# BLE1.net
KiCad netlist of a schematic drawn in EasyEDA Pro
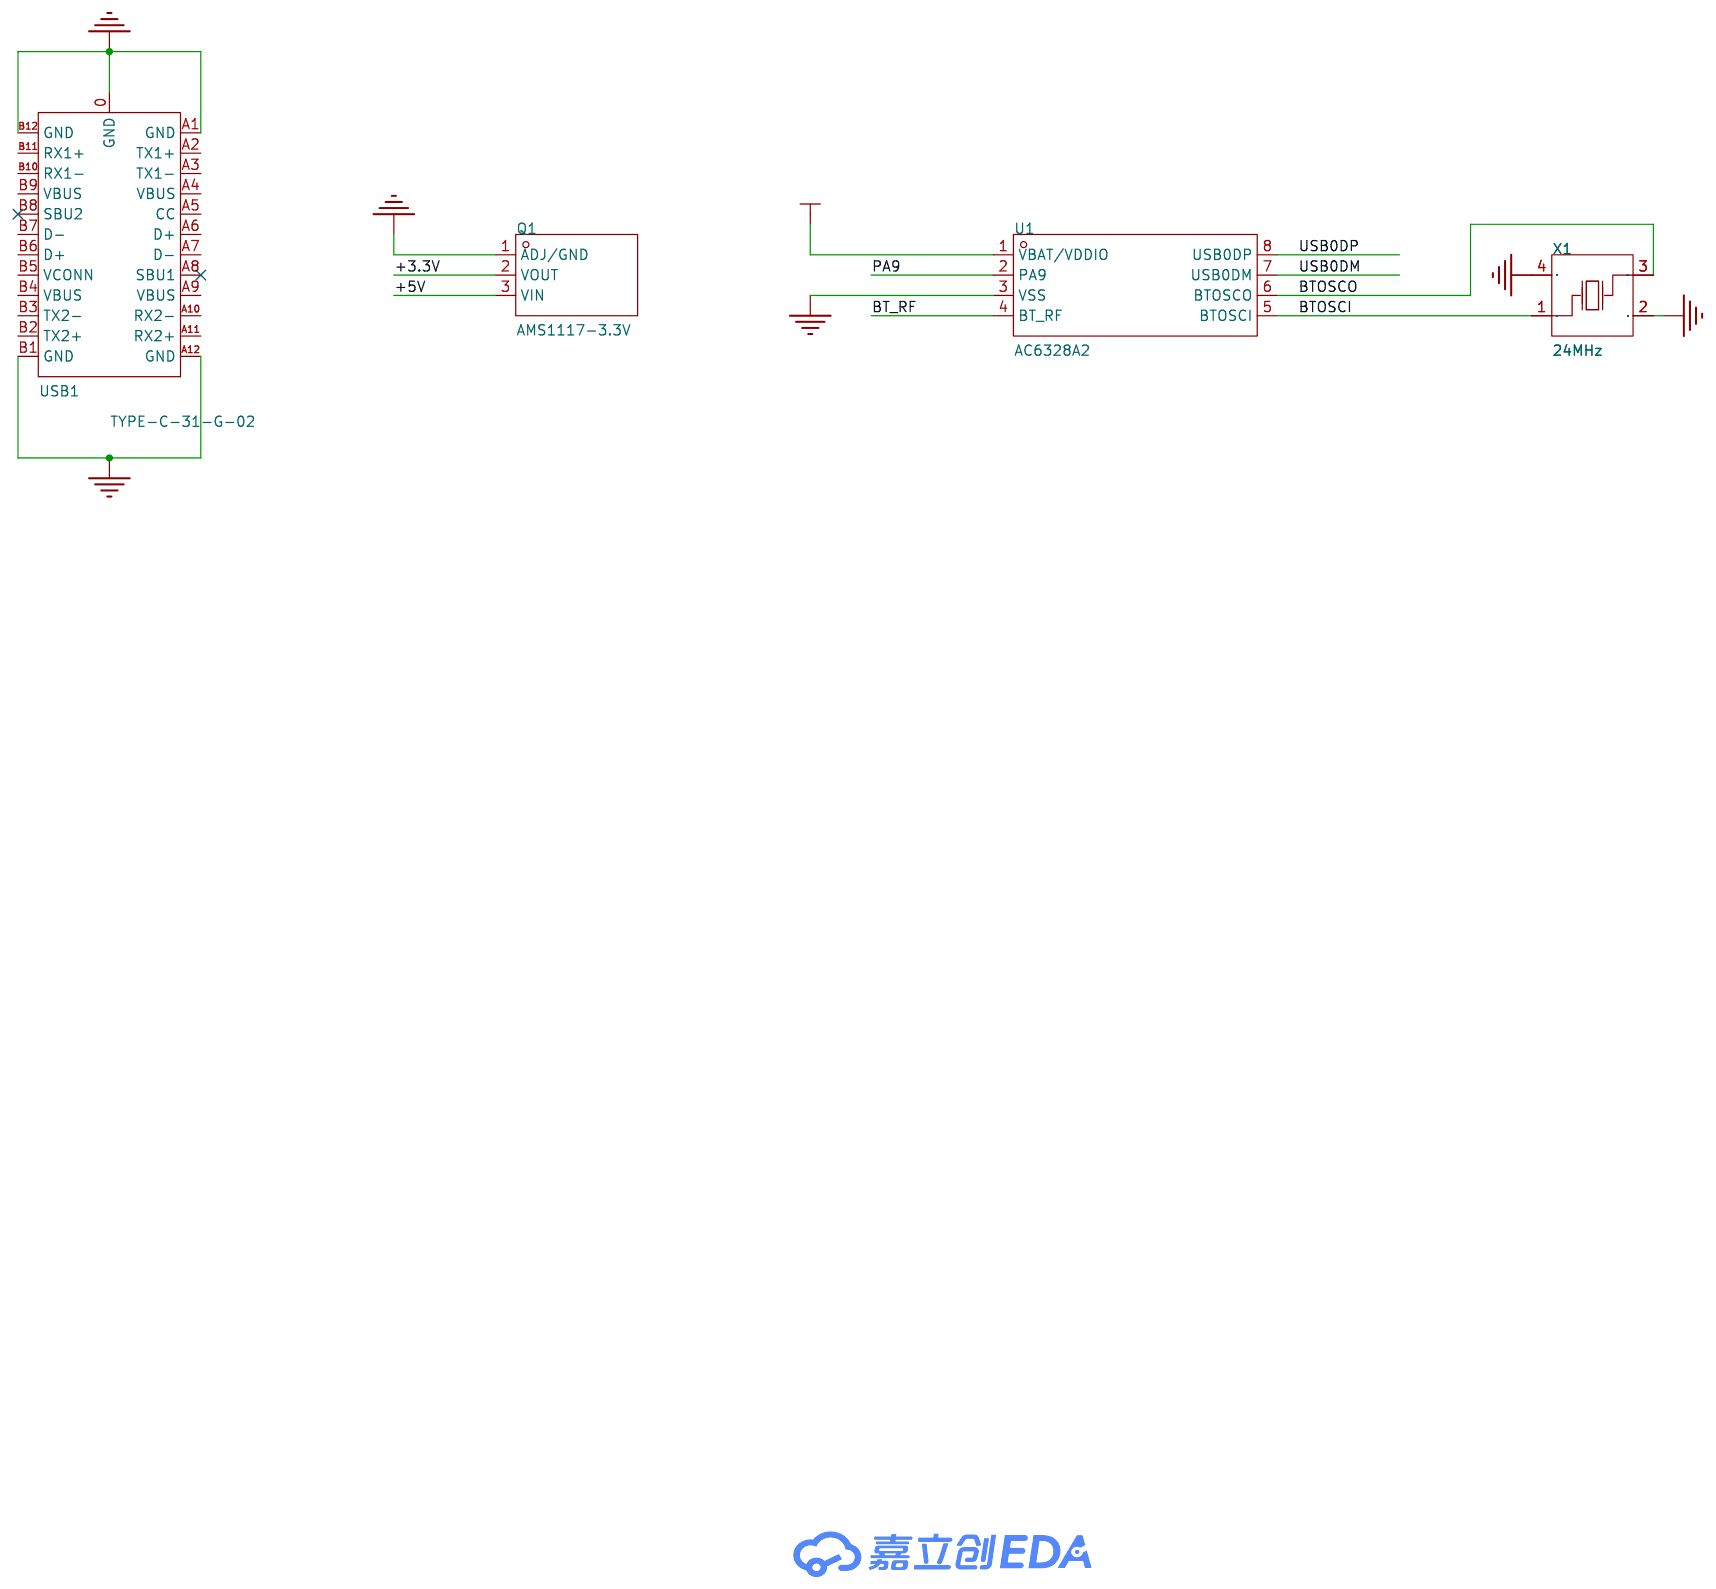
[diagram p0: schematic sheet]

(export (version "E")
  (design (tool "Eeschema 10.0.6"))
  (components
    (comp (ref "Q1")
      (value "AMS1117-3.3V")
      (footprint "easyedapro:SOT-89-3_L4.5-W2.5-P1.50-LS4.2-BR")
      (description "输出类型:固定;工作电压:18V;输出电压:3.3V;输出电流:1A;输出极性:正极;")
      (fields (field (name "Manufacturer") "MSKSEMI(美森科)"))
      (libsource (lib "easyedapro") (part "AMS1117-3.3V_C5120796"))
    )
    (comp (ref "U1")
      (value "AC6328A2")
      (footprint "easyedapro:SOP-8_L4.9-W3.9-P1.27-LS6.0-BL")
      (fields (field (name "Manufacturer") "JL(杰理)"))
      (libsource (lib "easyedapro") (part "AC6328A2"))
    )
    (comp (ref "USB1")
      (value "TYPE-C-31-G-02")
      (footprint "easyedapro:USB-C-SMD_TYPE-C-31-G-02")
      (description "连接器类型:Type-C;协议标准:-;公母:公;安装方式:夹板;触点数量:24P;端口数量:1;额定电流 - 电源:-;工作温度:-55°C~+85°C;")
      (fields (field (name "Manufacturer") "韩国韩荣"))
      (libsource (lib "easyedapro") (part "TYPE-C-31-G-02"))
    )
    (comp (ref "X1")
      (value "24MHz")
      (footprint "easyedapro:CRYSTAL-SMD_4P-L3.2-W2.5-BL")
      (description "晶振类型:贴片晶振;频率:24MHz;常温频差:±10ppm;负载电容:12pF;频率稳定度:±20ppm;")
      (fields (field (name "Manufacturer Part") "X322524MOB4SI") (field (name "Manufacturer") "YXC(扬兴晶振)"))
      (libsource (lib "easyedapro") (part "X322524MOB4SI"))
    )
  )
  (nets
    (net (code "1") (name "+3.3V") (class "Default")
      (node (ref "Q1") (pin "2") (pinfunction "VOUT_2") (pintype "unspecified"))
      (node (ref "U1") (pin "1") (pinfunction "VBAT/VDDIO_1") (pintype "unspecified"))
    )
    (net (code "2") (name "/+5V") (class "Default")
      (node (ref "Q1") (pin "3") (pinfunction "VIN_3") (pintype "unspecified"))
    )
    (net (code "3") (name "/BTOSCI") (class "Default")
      (node (ref "U1") (pin "5") (pinfunction "BTOSCI_5") (pintype "unspecified"))
      (node (ref "X1") (pin "1") (pinfunction "OSC1_1") (pintype "unspecified"))
    )
    (net (code "4") (name "/BTOSCO") (class "Default")
      (node (ref "U1") (pin "6") (pinfunction "BTOSCO_6") (pintype "unspecified"))
      (node (ref "X1") (pin "3") (pinfunction "OSC2_3") (pintype "unspecified"))
    )
    (net (code "5") (name "/BT_RF") (class "Default")
      (node (ref "U1") (pin "4") (pinfunction "BT_RF_4") (pintype "unspecified"))
    )
    (net (code "6") (name "/PA9") (class "Default")
      (node (ref "U1") (pin "2") (pinfunction "PA9_2") (pintype "unspecified"))
    )
    (net (code "7") (name "/USB0DM") (class "Default")
      (node (ref "U1") (pin "7") (pinfunction "USB0DM_7") (pintype "unspecified"))
    )
    (net (code "8") (name "/USB0DP") (class "Default")
      (node (ref "U1") (pin "8") (pinfunction "USB0DP_8") (pintype "unspecified"))
    )
    (net (code "9") (name "GND") (class "Default")
      (node (ref "Q1") (pin "1") (pinfunction "ADJ/GND_1") (pintype "unspecified"))
      (node (ref "U1") (pin "3") (pinfunction "VSS_3") (pintype "unspecified"))
      (node (ref "USB1") (pin "0") (pinfunction "GND_0") (pintype "unspecified"))
      (node (ref "USB1") (pin "A1") (pinfunction "GND_A1") (pintype "unspecified"))
      (node (ref "USB1") (pin "A12") (pinfunction "GND_A12") (pintype "unspecified"))
      (node (ref "USB1") (pin "B1") (pinfunction "GND_B1") (pintype "unspecified"))
      (node (ref "USB1") (pin "B12") (pinfunction "GND_B12") (pintype "unspecified"))
      (node (ref "X1") (pin "2") (pinfunction "GND_2") (pintype "unspecified"))
      (node (ref "X1") (pin "4") (pinfunction "GND_4") (pintype "unspecified"))
    )
    (net (code "10") (name "unconnected-(USB1-CC-PadA5)") (class "Default")
      (node (ref "USB1") (pin "A5") (pinfunction "CC_A5") (pintype "unspecified"))
    )
    (net (code "11") (name "unconnected-(USB1-D+-PadA6)") (class "Default")
      (node (ref "USB1") (pin "A6") (pinfunction "D+_A6") (pintype "unspecified"))
    )
    (net (code "12") (name "unconnected-(USB1-D+-PadB6)") (class "Default")
      (node (ref "USB1") (pin "B6") (pinfunction "D+_B6") (pintype "unspecified"))
    )
    (net (code "13") (name "unconnected-(USB1-D--PadA7)") (class "Default")
      (node (ref "USB1") (pin "A7") (pinfunction "D-_A7") (pintype "unspecified"))
    )
    (net (code "14") (name "unconnected-(USB1-D--PadB7)") (class "Default")
      (node (ref "USB1") (pin "B7") (pinfunction "D-_B7") (pintype "unspecified"))
    )
    (net (code "15") (name "unconnected-(USB1-RX1+-PadB11)") (class "Default")
      (node (ref "USB1") (pin "B11") (pinfunction "RX1+_B11") (pintype "unspecified"))
    )
    (net (code "16") (name "unconnected-(USB1-RX1--PadB10)") (class "Default")
      (node (ref "USB1") (pin "B10") (pinfunction "RX1-_B10") (pintype "unspecified"))
    )
    (net (code "17") (name "unconnected-(USB1-RX2+-PadA11)") (class "Default")
      (node (ref "USB1") (pin "A11") (pinfunction "RX2+_A11") (pintype "unspecified"))
    )
    (net (code "18") (name "unconnected-(USB1-RX2--PadA10)") (class "Default")
      (node (ref "USB1") (pin "A10") (pinfunction "RX2-_A10") (pintype "unspecified"))
    )
    (net (code "19") (name "unconnected-(USB1-SBU1-PadA8)") (class "Default")
      (node (ref "USB1") (pin "A8") (pinfunction "SBU1_A8") (pintype "unspecified+no_connect"))
    )
    (net (code "20") (name "unconnected-(USB1-SBU2-PadB8)") (class "Default")
      (node (ref "USB1") (pin "B8") (pinfunction "SBU2_B8") (pintype "unspecified+no_connect"))
    )
    (net (code "21") (name "unconnected-(USB1-TX1+-PadA2)") (class "Default")
      (node (ref "USB1") (pin "A2") (pinfunction "TX1+_A2") (pintype "unspecified"))
    )
    (net (code "22") (name "unconnected-(USB1-TX1--PadA3)") (class "Default")
      (node (ref "USB1") (pin "A3") (pinfunction "TX1-_A3") (pintype "unspecified"))
    )
    (net (code "23") (name "unconnected-(USB1-TX2+-PadB2)") (class "Default")
      (node (ref "USB1") (pin "B2") (pinfunction "TX2+_B2") (pintype "unspecified"))
    )
    (net (code "24") (name "unconnected-(USB1-TX2--PadB3)") (class "Default")
      (node (ref "USB1") (pin "B3") (pinfunction "TX2-_B3") (pintype "unspecified"))
    )
    (net (code "25") (name "unconnected-(USB1-VBUS-PadA4)") (class "Default")
      (node (ref "USB1") (pin "A4") (pinfunction "VBUS_A4") (pintype "unspecified"))
    )
    (net (code "26") (name "unconnected-(USB1-VBUS-PadA9)") (class "Default")
      (node (ref "USB1") (pin "A9") (pinfunction "VBUS_A9") (pintype "unspecified"))
    )
    (net (code "27") (name "unconnected-(USB1-VBUS-PadB4)") (class "Default")
      (node (ref "USB1") (pin "B4") (pinfunction "VBUS_B4") (pintype "unspecified"))
    )
    (net (code "28") (name "unconnected-(USB1-VBUS-PadB9)") (class "Default")
      (node (ref "USB1") (pin "B9") (pinfunction "VBUS_B9") (pintype "unspecified"))
    )
    (net (code "29") (name "unconnected-(USB1-VCONN-PadB5)") (class "Default")
      (node (ref "USB1") (pin "B5") (pinfunction "VCONN_B5") (pintype "unspecified"))
    )
  )
)
